# datalore.net
KiCad netlist of a schematic drawn in EAGLE
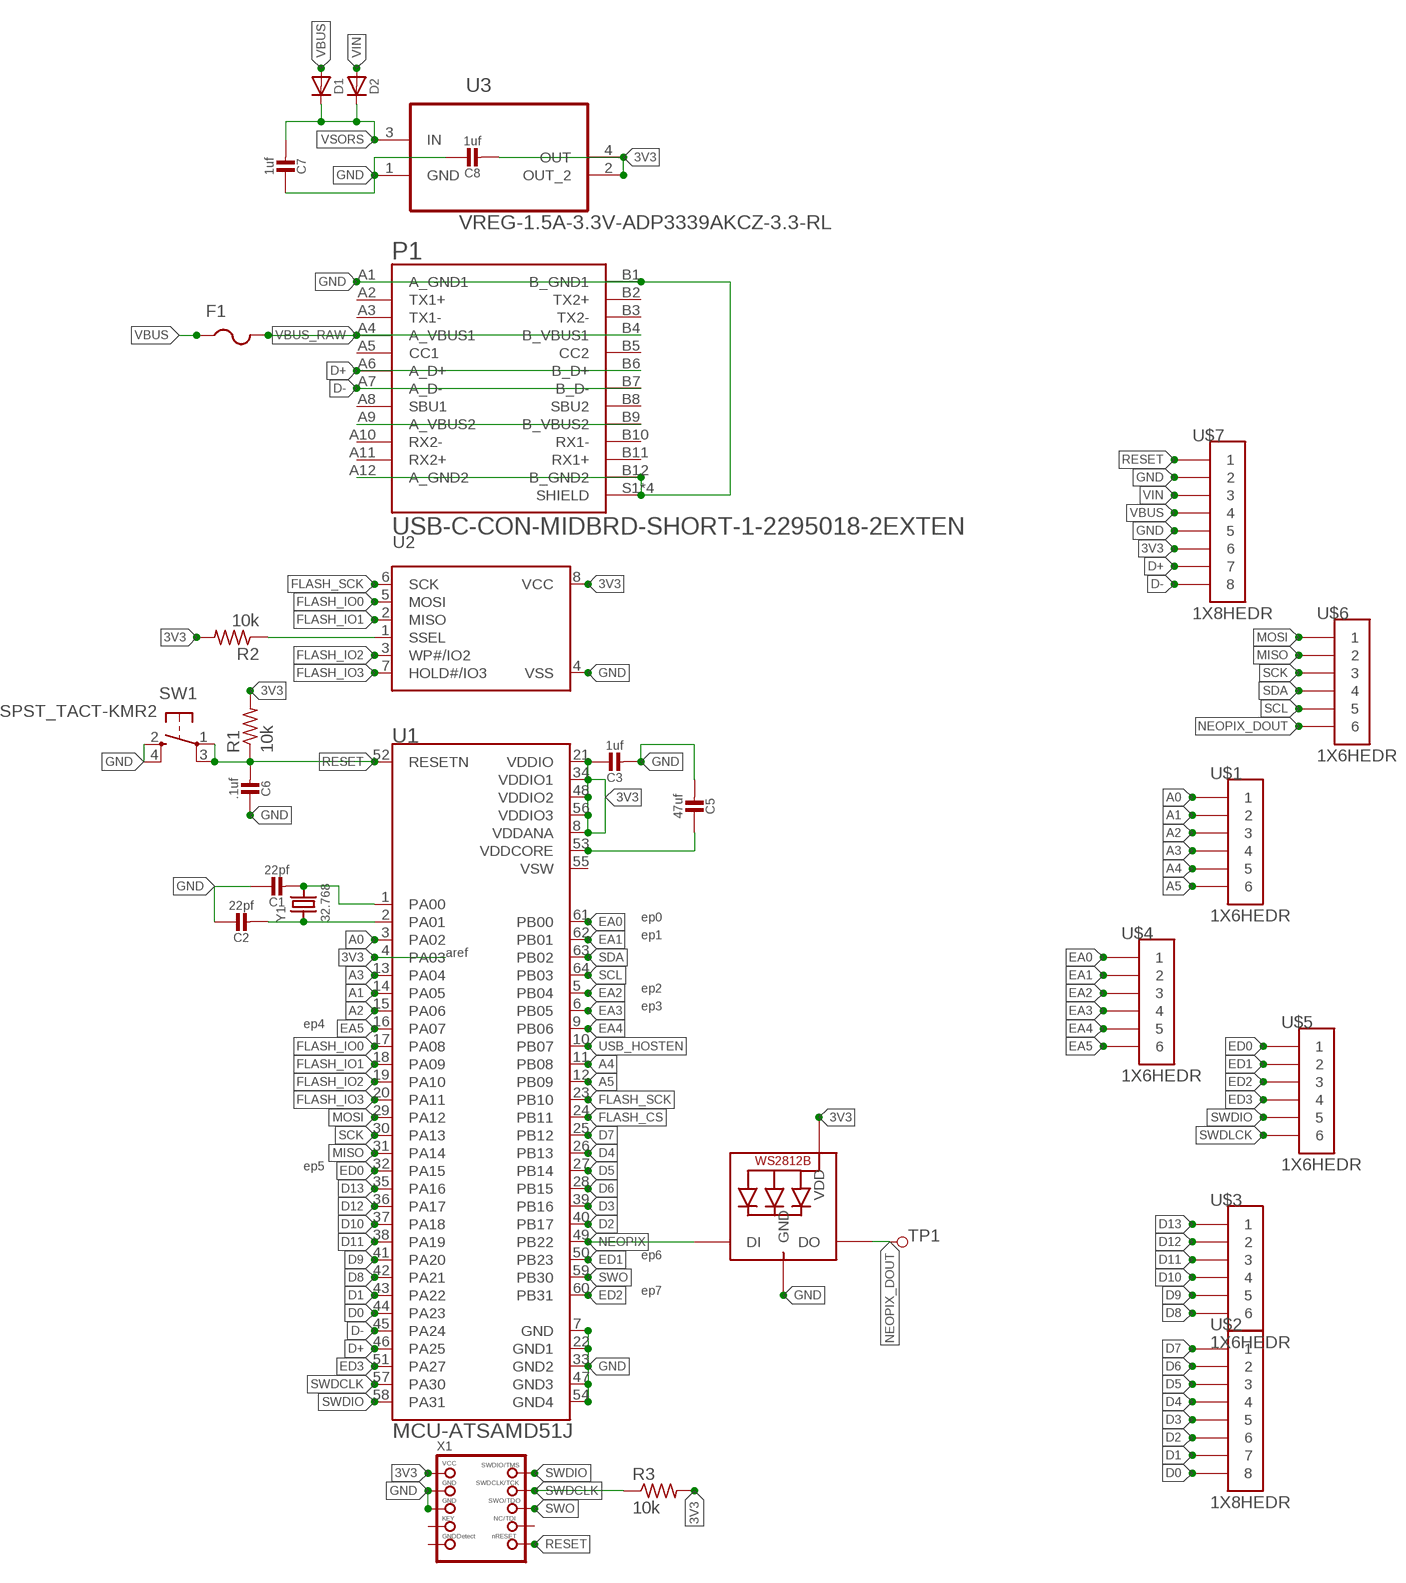
[diagram p0: schematic, sheet 1]

(export (version "E")
  (design (tool "Eeschema 10.0.6"))
  (components
    (comp (ref "C1")
      (value "22pf")
      (footprint "eagle-import:MICROBUILDER__0805")
      (libsource (lib "eagle-import") (part "C-US__0805"))
    )
    (comp (ref "C2")
      (value "22pf")
      (footprint "eagle-import:MICROBUILDER__0805")
      (libsource (lib "eagle-import") (part "C-US__0805"))
    )
    (comp (ref "C3")
      (value "1uf")
      (footprint "eagle-import:MICROBUILDER__0805")
      (libsource (lib "eagle-import") (part "C-US__0805"))
    )
    (comp (ref "C5")
      (value "47uf")
      (footprint "eagle-import:MICROBUILDER__0805")
      (libsource (lib "eagle-import") (part "C-US__0805"))
    )
    (comp (ref "C6")
      (value ".1uf")
      (footprint "eagle-import:MICROBUILDER__0805")
      (libsource (lib "eagle-import") (part "C-US__0805"))
    )
    (comp (ref "C7")
      (value "1uf")
      (footprint "eagle-import:MICROBUILDER__0805")
      (libsource (lib "eagle-import") (part "C-US__0805"))
    )
    (comp (ref "C8")
      (value "1uf")
      (footprint "eagle-import:MICROBUILDER__0805")
      (libsource (lib "eagle-import") (part "C-US__0805"))
    )
    (comp (ref "D1")
      (value "DIODESOD-123")
      (footprint "eagle-import:SOD-123")
      (libsource (lib "eagle-import") (part "DIODESOD-123"))
    )
    (comp (ref "D2")
      (value "DIODESOD-123")
      (footprint "eagle-import:SOD-123")
      (libsource (lib "eagle-import") (part "DIODESOD-123"))
    )
    (comp (ref "F1")
      (value "PTCFUSE-1206")
      (footprint "eagle-import:R1206")
      (libsource (lib "eagle-import") (part "PTCFUSE-1206"))
    )
    (comp (ref "LED1")
      (value "LED-NEO-WS2812B3535")
      (footprint "eagle-import:LED3535")
      (libsource (lib "eagle-import") (part "LED-NEO-WS2812B3535"))
    )
    (comp (ref "P1")
      (value "USB-C-CON-MIDBRD-SHORT-1-2295018-2EXTEN")
      (footprint "eagle-import:TE_1-2295018-2_EXTEN")
      (libsource (lib "eagle-import") (part "USB-C-CON-MIDBRD-SHORT-1-2295018-2EXTEN"))
    )
    (comp (ref "R1")
      (value "10k")
      (footprint "eagle-import:R0805")
      (libsource (lib "eagle-import") (part "R-US_R0805"))
    )
    (comp (ref "R2")
      (value "10k")
      (footprint "eagle-import:R0805")
      (libsource (lib "eagle-import") (part "R-US_R0805"))
    )
    (comp (ref "R3")
      (value "10k")
      (footprint "eagle-import:R0805")
      (libsource (lib "eagle-import") (part "R-US_R0805"))
    )
    (comp (ref "SW1")
      (value "SPST_TACT-KMR2")
      (footprint "eagle-import:KMR2")
      (libsource (lib "eagle-import") (part "SPST_TACT-KMR2"))
    )
    (comp (ref "TP1")
      (value "TESTPOINT_1X1")
      (footprint "eagle-import:1X1_POGO")
      (libsource (lib "eagle-import") (part "TESTPOINT_1X1"))
    )
    (comp (ref "U$1")
      (value "1X6HEDR")
      (footprint "eagle-import:1X6_HEDR")
      (libsource (lib "eagle-import") (part "1X6HEDR"))
    )
    (comp (ref "U$2")
      (value "1X8HEDR")
      (footprint "eagle-import:1X8_HEDR")
      (libsource (lib "eagle-import") (part "1X8HEDR"))
    )
    (comp (ref "U$3")
      (value "1X6HEDR")
      (footprint "eagle-import:1X6_HEDR")
      (libsource (lib "eagle-import") (part "1X6HEDR"))
    )
    (comp (ref "U$4")
      (value "1X6HEDR")
      (footprint "eagle-import:1X6_HEDR")
      (libsource (lib "eagle-import") (part "1X6HEDR"))
    )
    (comp (ref "U$5")
      (value "1X6HEDR")
      (footprint "eagle-import:1X6_HEDR")
      (libsource (lib "eagle-import") (part "1X6HEDR"))
    )
    (comp (ref "U$6")
      (value "1X6HEDR")
      (footprint "eagle-import:1X6_HEDR")
      (libsource (lib "eagle-import") (part "1X6HEDR"))
    )
    (comp (ref "U$7")
      (value "1X8HEDR")
      (footprint "eagle-import:1X8_HEDR")
      (libsource (lib "eagle-import") (part "1X8HEDR"))
    )
    (comp (ref "U1")
      (value "MCU-ATSAMD51J")
      (footprint "eagle-import:QFP50P1200X1200X120-64N")
      (fields (field (name "MF") "Microchip") (field (name "MP") "ATSAMD51J20A-AU"))
      (libsource (lib "eagle-import") (part "MCU-ATSAMD51J"))
    )
    (comp (ref "U2")
      (value "FLASH-SPI-SOIC8208MIL")
      (footprint "eagle-import:SOIC8_208MIL")
      (libsource (lib "eagle-import") (part "FLASH-SPI-SOIC8208MIL"))
    )
    (comp (ref "U3")
      (value "VREG-1.5A-3.3V-ADP3339AKCZ-3.3-RL")
      (footprint "eagle-import:SOT230P700X180-4N")
      (fields (field (name "MF") "Analog Devices") (field (name "MP") "ADP3339AKCZ-3.3-RL"))
      (libsource (lib "eagle-import") (part "VREG-1.5A-3.3V-ADP3339AKCZ-3.3-RL"))
    )
    (comp (ref "X1")
      (value "INTRFC-JTAG-CORTEXBOXPOSTS")
      (footprint "eagle-import:2X05_1.27MM_BOX_POSTS")
      (libsource (lib "eagle-import") (part "INTRFC-JTAG-CORTEXBOXPOSTS"))
    )
    (comp (ref "Y1")
      (value "32.768")
      (footprint "eagle-import:MICROBUILDER_CRYSTAL_4.9X1.8")
      (libsource (lib "eagle-import") (part "XTAL_ADA4.9X1.8"))
    )
  )
  (nets
    (net (code "1") (name "/VSW") (class "Default")
      (node (ref "U1") (pin "55") (pinfunction "VSW_55") (pintype "power_in"))
    )
    (net (code "2") (name "3V3") (class "Default")
      (node (ref "C3") (pin "1") (pinfunction "1_1") (pintype "passive"))
      (node (ref "C8") (pin "2") (pinfunction "2_2") (pintype "passive"))
      (node (ref "LED1") (pin "2") (pinfunction "VDD_2") (pintype "power_in"))
      (node (ref "R1") (pin "2") (pinfunction "2_2") (pintype "passive"))
      (node (ref "R2") (pin "2") (pinfunction "2_2") (pintype "passive"))
      (node (ref "R3") (pin "2") (pinfunction "2_2") (pintype "passive"))
      (node (ref "U$7") (pin "6") (pinfunction "6_6") (pintype "bidirectional"))
      (node (ref "U1") (pin "21") (pinfunction "VDDIO_21") (pintype "power_in"))
      (node (ref "U1") (pin "34") (pinfunction "VDDIO1_34") (pintype "power_in"))
      (node (ref "U1") (pin "4") (pinfunction "PA03_4") (pintype "bidirectional"))
      (node (ref "U1") (pin "48") (pinfunction "VDDIO2_48") (pintype "power_in"))
      (node (ref "U1") (pin "56") (pinfunction "VDDIO3_56") (pintype "power_in"))
      (node (ref "U1") (pin "8") (pinfunction "VDDANA_8") (pintype "power_in"))
      (node (ref "U2") (pin "8") (pinfunction "VCC_8") (pintype "bidirectional"))
      (node (ref "U3") (pin "2") (pinfunction "OUT_2_2") (pintype "output"))
      (node (ref "U3") (pin "4") (pinfunction "OUT_4") (pintype "output"))
      (node (ref "X1") (pin "1") (pinfunction "VCC_1") (pintype "power_in"))
    )
    (net (code "3") (name "A0") (class "Default")
      (node (ref "U$1") (pin "1") (pinfunction "1_1") (pintype "bidirectional"))
      (node (ref "U1") (pin "3") (pinfunction "PA02_3") (pintype "bidirectional"))
    )
    (net (code "4") (name "A1") (class "Default")
      (node (ref "U$1") (pin "2") (pinfunction "2_2") (pintype "bidirectional"))
      (node (ref "U1") (pin "14") (pinfunction "PA05_14") (pintype "bidirectional"))
    )
    (net (code "5") (name "A2") (class "Default")
      (node (ref "U$1") (pin "3") (pinfunction "3_3") (pintype "bidirectional"))
      (node (ref "U1") (pin "15") (pinfunction "PA06_15") (pintype "bidirectional"))
    )
    (net (code "6") (name "A3") (class "Default")
      (node (ref "U$1") (pin "4") (pinfunction "4_4") (pintype "bidirectional"))
      (node (ref "U1") (pin "13") (pinfunction "PA04_13") (pintype "bidirectional"))
    )
    (net (code "7") (name "A4") (class "Default")
      (node (ref "U$1") (pin "5") (pinfunction "5_5") (pintype "bidirectional"))
      (node (ref "U1") (pin "11") (pinfunction "PB08_11") (pintype "bidirectional"))
    )
    (net (code "8") (name "A5") (class "Default")
      (node (ref "U$1") (pin "6") (pinfunction "6_6") (pintype "bidirectional"))
      (node (ref "U1") (pin "12") (pinfunction "PB09_12") (pintype "bidirectional"))
    )
    (net (code "9") (name "D+") (class "Default")
      (node (ref "P1") (pin "A6") (pinfunction "A_D+_A6") (pintype "passive"))
      (node (ref "P1") (pin "B6") (pinfunction "B_D+_B6") (pintype "passive"))
      (node (ref "U$7") (pin "7") (pinfunction "7_7") (pintype "bidirectional"))
      (node (ref "U1") (pin "46") (pinfunction "PA25_46") (pintype "bidirectional"))
    )
    (net (code "10") (name "D-") (class "Default")
      (node (ref "P1") (pin "A7") (pinfunction "A_D-_A7") (pintype "passive"))
      (node (ref "P1") (pin "B7") (pinfunction "B_D-_B7") (pintype "passive"))
      (node (ref "U$7") (pin "8") (pinfunction "8_8") (pintype "bidirectional"))
      (node (ref "U1") (pin "45") (pinfunction "PA24_45") (pintype "bidirectional"))
    )
    (net (code "11") (name "D0") (class "Default")
      (node (ref "U$2") (pin "8") (pinfunction "8_8") (pintype "bidirectional"))
      (node (ref "U1") (pin "44") (pinfunction "PA23_44") (pintype "bidirectional"))
    )
    (net (code "12") (name "D1") (class "Default")
      (node (ref "U$2") (pin "7") (pinfunction "7_7") (pintype "bidirectional"))
      (node (ref "U1") (pin "43") (pinfunction "PA22_43") (pintype "bidirectional"))
    )
    (net (code "13") (name "D2") (class "Default")
      (node (ref "U$2") (pin "6") (pinfunction "6_6") (pintype "bidirectional"))
      (node (ref "U1") (pin "40") (pinfunction "PB17_40") (pintype "bidirectional"))
    )
    (net (code "14") (name "D3") (class "Default")
      (node (ref "U$2") (pin "5") (pinfunction "5_5") (pintype "bidirectional"))
      (node (ref "U1") (pin "39") (pinfunction "PB16_39") (pintype "bidirectional"))
    )
    (net (code "15") (name "D4") (class "Default")
      (node (ref "U$2") (pin "4") (pinfunction "4_4") (pintype "bidirectional"))
      (node (ref "U1") (pin "26") (pinfunction "PB13_26") (pintype "bidirectional"))
    )
    (net (code "16") (name "D5") (class "Default")
      (node (ref "U$2") (pin "3") (pinfunction "3_3") (pintype "bidirectional"))
      (node (ref "U1") (pin "27") (pinfunction "PB14_27") (pintype "bidirectional"))
    )
    (net (code "17") (name "D6") (class "Default")
      (node (ref "U$2") (pin "2") (pinfunction "2_2") (pintype "bidirectional"))
      (node (ref "U1") (pin "28") (pinfunction "PB15_28") (pintype "bidirectional"))
    )
    (net (code "18") (name "D7") (class "Default")
      (node (ref "U$2") (pin "1") (pinfunction "1_1") (pintype "bidirectional"))
      (node (ref "U1") (pin "25") (pinfunction "PB12_25") (pintype "bidirectional"))
    )
    (net (code "19") (name "D8") (class "Default")
      (node (ref "U$3") (pin "6") (pinfunction "6_6") (pintype "bidirectional"))
      (node (ref "U1") (pin "42") (pinfunction "PA21_42") (pintype "bidirectional"))
    )
    (net (code "20") (name "D9") (class "Default")
      (node (ref "U$3") (pin "5") (pinfunction "5_5") (pintype "bidirectional"))
      (node (ref "U1") (pin "41") (pinfunction "PA20_41") (pintype "bidirectional"))
    )
    (net (code "21") (name "D10") (class "Default")
      (node (ref "U$3") (pin "4") (pinfunction "4_4") (pintype "bidirectional"))
      (node (ref "U1") (pin "37") (pinfunction "PA18_37") (pintype "bidirectional"))
    )
    (net (code "22") (name "D11") (class "Default")
      (node (ref "U$3") (pin "3") (pinfunction "3_3") (pintype "bidirectional"))
      (node (ref "U1") (pin "38") (pinfunction "PA19_38") (pintype "bidirectional"))
    )
    (net (code "23") (name "D12") (class "Default")
      (node (ref "U$3") (pin "2") (pinfunction "2_2") (pintype "bidirectional"))
      (node (ref "U1") (pin "36") (pinfunction "PA17_36") (pintype "bidirectional"))
    )
    (net (code "24") (name "D13") (class "Default")
      (node (ref "U$3") (pin "1") (pinfunction "1_1") (pintype "bidirectional"))
      (node (ref "U1") (pin "35") (pinfunction "PA16_35") (pintype "bidirectional"))
    )
    (net (code "25") (name "EA0") (class "Default")
      (node (ref "U$4") (pin "1") (pinfunction "1_1") (pintype "bidirectional"))
      (node (ref "U1") (pin "61") (pinfunction "PB00_61") (pintype "bidirectional"))
    )
    (net (code "26") (name "EA1") (class "Default")
      (node (ref "U$4") (pin "2") (pinfunction "2_2") (pintype "bidirectional"))
      (node (ref "U1") (pin "62") (pinfunction "PB01_62") (pintype "bidirectional"))
    )
    (net (code "27") (name "EA2") (class "Default")
      (node (ref "U$4") (pin "3") (pinfunction "3_3") (pintype "bidirectional"))
      (node (ref "U1") (pin "5") (pinfunction "PB04_5") (pintype "bidirectional"))
    )
    (net (code "28") (name "EA3") (class "Default")
      (node (ref "U$4") (pin "4") (pinfunction "4_4") (pintype "bidirectional"))
      (node (ref "U1") (pin "6") (pinfunction "PB05_6") (pintype "bidirectional"))
    )
    (net (code "29") (name "EA4") (class "Default")
      (node (ref "U$4") (pin "5") (pinfunction "5_5") (pintype "bidirectional"))
      (node (ref "U1") (pin "9") (pinfunction "PB06_9") (pintype "bidirectional"))
    )
    (net (code "30") (name "EA5") (class "Default")
      (node (ref "U$4") (pin "6") (pinfunction "6_6") (pintype "bidirectional"))
      (node (ref "U1") (pin "16") (pinfunction "PA07_16") (pintype "bidirectional"))
    )
    (net (code "31") (name "ED0") (class "Default")
      (node (ref "U$5") (pin "1") (pinfunction "1_1") (pintype "bidirectional"))
      (node (ref "U1") (pin "32") (pinfunction "PA15_32") (pintype "bidirectional"))
    )
    (net (code "32") (name "ED1") (class "Default")
      (node (ref "U$5") (pin "2") (pinfunction "2_2") (pintype "bidirectional"))
      (node (ref "U1") (pin "50") (pinfunction "PB23_50") (pintype "bidirectional"))
    )
    (net (code "33") (name "ED2") (class "Default")
      (node (ref "U$5") (pin "3") (pinfunction "3_3") (pintype "bidirectional"))
      (node (ref "U1") (pin "60") (pinfunction "PB31_60") (pintype "bidirectional"))
    )
    (net (code "34") (name "ED3") (class "Default")
      (node (ref "U$5") (pin "4") (pinfunction "4_4") (pintype "bidirectional"))
      (node (ref "U1") (pin "51") (pinfunction "PA27_51") (pintype "bidirectional"))
    )
    (net (code "35") (name "FLASH_CS") (class "Default")
      (node (ref "U1") (pin "24") (pinfunction "PB11_24") (pintype "bidirectional"))
    )
    (net (code "36") (name "FLASH_IO0") (class "Default")
      (node (ref "U1") (pin "17") (pinfunction "PA08_17") (pintype "bidirectional"))
      (node (ref "U2") (pin "5") (pinfunction "MOSI_5") (pintype "bidirectional"))
    )
    (net (code "37") (name "FLASH_IO1") (class "Default")
      (node (ref "U1") (pin "18") (pinfunction "PA09_18") (pintype "bidirectional"))
      (node (ref "U2") (pin "2") (pinfunction "MISO_2") (pintype "bidirectional"))
    )
    (net (code "38") (name "FLASH_IO2") (class "Default")
      (node (ref "U1") (pin "19") (pinfunction "PA10_19") (pintype "bidirectional"))
      (node (ref "U2") (pin "3") (pinfunction "WP#/IO2_3") (pintype "bidirectional"))
    )
    (net (code "39") (name "FLASH_IO3") (class "Default")
      (node (ref "U1") (pin "20") (pinfunction "PA11_20") (pintype "bidirectional"))
      (node (ref "U2") (pin "7") (pinfunction "HOLD#/IO3_7") (pintype "bidirectional"))
    )
    (net (code "40") (name "FLASH_SCK") (class "Default")
      (node (ref "U1") (pin "23") (pinfunction "PB10_23") (pintype "bidirectional"))
      (node (ref "U2") (pin "6") (pinfunction "SCK_6") (pintype "bidirectional"))
    )
    (net (code "41") (name "GND") (class "Default")
      (node (ref "C1") (pin "1") (pinfunction "1_1") (pintype "passive"))
      (node (ref "C2") (pin "1") (pinfunction "1_1") (pintype "passive"))
      (node (ref "C3") (pin "2") (pinfunction "2_2") (pintype "passive"))
      (node (ref "C5") (pin "2") (pinfunction "2_2") (pintype "passive"))
      (node (ref "C6") (pin "1") (pinfunction "1_1") (pintype "passive"))
      (node (ref "C7") (pin "1") (pinfunction "1_1") (pintype "passive"))
      (node (ref "C8") (pin "1") (pinfunction "1_1") (pintype "passive"))
      (node (ref "LED1") (pin "4") (pinfunction "GND_4") (pintype "power_in"))
      (node (ref "P1") (pin "A1") (pinfunction "A_GND1_A1") (pintype "passive"))
      (node (ref "P1") (pin "A12") (pinfunction "A_GND2_A12") (pintype "passive"))
      (node (ref "P1") (pin "B1") (pinfunction "B_GND1_B1") (pintype "passive"))
      (node (ref "P1") (pin "B12") (pinfunction "B_GND2_B12") (pintype "passive"))
      (node (ref "P1") (pin "S1") (pinfunction "SHIELD_S1") (pintype "passive"))
      (node (ref "P1") (pin "S2") (pinfunction "SHIELD_S2") (pintype "passive"))
      (node (ref "P1") (pin "S3") (pinfunction "SHIELD_S3") (pintype "passive"))
      (node (ref "P1") (pin "S4") (pinfunction "SHIELD_S4") (pintype "passive"))
      (node (ref "SW1") (pin "2") (pinfunction "S_2") (pintype "passive"))
      (node (ref "SW1") (pin "4") (pinfunction "S1_4") (pintype "passive"))
      (node (ref "U$7") (pin "2") (pinfunction "2_2") (pintype "bidirectional"))
      (node (ref "U$7") (pin "5") (pinfunction "5_5") (pintype "bidirectional"))
      (node (ref "U1") (pin "22") (pinfunction "GND1_22") (pintype "power_in"))
      (node (ref "U1") (pin "33") (pinfunction "GND2_33") (pintype "power_in"))
      (node (ref "U1") (pin "47") (pinfunction "GND3_47") (pintype "power_in"))
      (node (ref "U1") (pin "54") (pinfunction "GND4_54") (pintype "power_in"))
      (node (ref "U1") (pin "7") (pinfunction "GND_7") (pintype "power_in"))
      (node (ref "U2") (pin "4") (pinfunction "VSS_4") (pintype "bidirectional"))
      (node (ref "U3") (pin "1") (pinfunction "GND_1") (pintype "passive"))
      (node (ref "X1") (pin "3") (pinfunction "GND_3") (pintype "power_in"))
      (node (ref "X1") (pin "5") (pinfunction "GND_5") (pintype "power_in"))
    )
    (net (code "42") (name "MISO") (class "Default")
      (node (ref "U$6") (pin "2") (pinfunction "2_2") (pintype "bidirectional"))
      (node (ref "U1") (pin "31") (pinfunction "PA14_31") (pintype "bidirectional"))
    )
    (net (code "43") (name "MOSI") (class "Default")
      (node (ref "U$6") (pin "1") (pinfunction "1_1") (pintype "bidirectional"))
      (node (ref "U1") (pin "29") (pinfunction "PA12_29") (pintype "bidirectional"))
    )
    (net (code "44") (name "NEOPIX") (class "Default")
      (node (ref "LED1") (pin "1") (pinfunction "DI_1") (pintype "input"))
      (node (ref "U1") (pin "49") (pinfunction "PB22_49") (pintype "bidirectional"))
    )
    (net (code "45") (name "NEOPIX_DOUT") (class "Default")
      (node (ref "LED1") (pin "3") (pinfunction "DO_3") (pintype "output"))
      (node (ref "TP1") (pin "1") (pinfunction "P1_1") (pintype "bidirectional"))
      (node (ref "U$6") (pin "6") (pinfunction "6_6") (pintype "bidirectional"))
    )
    (net (code "46") (name "Net-(P1-A_VBUS2)") (class "Default")
      (node (ref "P1") (pin "A9") (pinfunction "A_VBUS2_A9") (pintype "passive"))
      (node (ref "P1") (pin "B9") (pinfunction "B_VBUS2_B9") (pintype "passive"))
    )
    (net (code "47") (name "Net-(U1-PA00)") (class "Default")
      (node (ref "C1") (pin "2") (pinfunction "2_2") (pintype "passive"))
      (node (ref "U1") (pin "1") (pinfunction "PA00_1") (pintype "bidirectional"))
      (node (ref "Y1") (pin "2") (pinfunction "2_2") (pintype "passive"))
    )
    (net (code "48") (name "Net-(U1-PA01)") (class "Default")
      (node (ref "C2") (pin "2") (pinfunction "2_2") (pintype "passive"))
      (node (ref "U1") (pin "2") (pinfunction "PA01_2") (pintype "bidirectional"))
      (node (ref "Y1") (pin "1") (pinfunction "1_1") (pintype "passive"))
    )
    (net (code "49") (name "Net-(U1-VDDCORE)") (class "Default")
      (node (ref "C5") (pin "1") (pinfunction "1_1") (pintype "passive"))
      (node (ref "U1") (pin "53") (pinfunction "VDDCORE_53") (pintype "power_in"))
    )
    (net (code "50") (name "Net-(U2-SSEL)") (class "Default")
      (node (ref "R2") (pin "1") (pinfunction "1_1") (pintype "passive"))
      (node (ref "U2") (pin "1") (pinfunction "SSEL_1") (pintype "bidirectional"))
    )
    (net (code "51") (name "RESET") (class "Default")
      (node (ref "C6") (pin "2") (pinfunction "2_2") (pintype "passive"))
      (node (ref "R1") (pin "1") (pinfunction "1_1") (pintype "passive"))
      (node (ref "SW1") (pin "1") (pinfunction "P_1") (pintype "passive"))
      (node (ref "SW1") (pin "3") (pinfunction "P1_3") (pintype "passive"))
      (node (ref "U$7") (pin "1") (pinfunction "1_1") (pintype "bidirectional"))
      (node (ref "U1") (pin "52") (pinfunction "RESETN_52") (pintype "input"))
      (node (ref "X1") (pin "10") (pinfunction "NRESET_10") (pintype "bidirectional"))
    )
    (net (code "52") (name "SCK") (class "Default")
      (node (ref "U$6") (pin "3") (pinfunction "3_3") (pintype "bidirectional"))
      (node (ref "U1") (pin "30") (pinfunction "PA13_30") (pintype "bidirectional"))
    )
    (net (code "53") (name "SCL") (class "Default")
      (node (ref "U$6") (pin "5") (pinfunction "5_5") (pintype "bidirectional"))
      (node (ref "U1") (pin "64") (pinfunction "PB03_64") (pintype "bidirectional"))
    )
    (net (code "54") (name "SDA") (class "Default")
      (node (ref "U$6") (pin "4") (pinfunction "4_4") (pintype "bidirectional"))
      (node (ref "U1") (pin "63") (pinfunction "PB02_63") (pintype "bidirectional"))
    )
    (net (code "55") (name "SWDCLK") (class "Default")
      (node (ref "R3") (pin "1") (pinfunction "1_1") (pintype "passive"))
      (node (ref "U1") (pin "57") (pinfunction "PA30_57") (pintype "bidirectional"))
      (node (ref "X1") (pin "4") (pinfunction "SWDCLK_4") (pintype "bidirectional"))
    )
    (net (code "56") (name "SWDIO") (class "Default")
      (node (ref "U$5") (pin "5") (pinfunction "5_5") (pintype "bidirectional"))
      (node (ref "U1") (pin "58") (pinfunction "PA31_58") (pintype "bidirectional"))
      (node (ref "X1") (pin "2") (pinfunction "SWDIO_2") (pintype "bidirectional"))
    )
    (net (code "57") (name "SWDLCK") (class "Default")
      (node (ref "U$5") (pin "6") (pinfunction "6_6") (pintype "bidirectional"))
    )
    (net (code "58") (name "SWO") (class "Default")
      (node (ref "U1") (pin "59") (pinfunction "PB30_59") (pintype "bidirectional"))
      (node (ref "X1") (pin "6") (pinfunction "SWO_6") (pintype "bidirectional"))
    )
    (net (code "59") (name "USB_HOSTEN") (class "Default")
      (node (ref "U1") (pin "10") (pinfunction "PB07_10") (pintype "bidirectional"))
    )
    (net (code "60") (name "VBUS") (class "Default")
      (node (ref "D1") (pin "A") (pinfunction "A_A") (pintype "passive"))
      (node (ref "F1") (pin "1") (pinfunction "1_1") (pintype "passive"))
      (node (ref "U$7") (pin "4") (pinfunction "4_4") (pintype "bidirectional"))
    )
    (net (code "61") (name "VBUS_RAW") (class "Default")
      (node (ref "F1") (pin "2") (pinfunction "2_2") (pintype "passive"))
      (node (ref "P1") (pin "A4") (pinfunction "A_VBUS1_A4") (pintype "passive"))
      (node (ref "P1") (pin "B4") (pinfunction "B_VBUS1_B4") (pintype "passive"))
    )
    (net (code "62") (name "VIN") (class "Default")
      (node (ref "D2") (pin "A") (pinfunction "A_A") (pintype "passive"))
      (node (ref "U$7") (pin "3") (pinfunction "3_3") (pintype "bidirectional"))
    )
    (net (code "63") (name "VSORS") (class "Default")
      (node (ref "C7") (pin "2") (pinfunction "2_2") (pintype "passive"))
      (node (ref "D1") (pin "C") (pinfunction "C_C") (pintype "passive"))
      (node (ref "D2") (pin "C") (pinfunction "C_C") (pintype "passive"))
      (node (ref "U3") (pin "3") (pinfunction "IN_3") (pintype "input"))
    )
    (net (code "64") (name "unconnected-(P1-CC1-PadA5)") (class "Default")
      (node (ref "P1") (pin "A5") (pinfunction "CC1_A5") (pintype "passive"))
    )
    (net (code "65") (name "unconnected-(P1-CC2-PadB5)") (class "Default")
      (node (ref "P1") (pin "B5") (pinfunction "CC2_B5") (pintype "passive"))
    )
    (net (code "66") (name "unconnected-(P1-RX1+-PadB11)") (class "Default")
      (node (ref "P1") (pin "B11") (pinfunction "RX1+_B11") (pintype "passive"))
    )
    (net (code "67") (name "unconnected-(P1-RX1--PadB10)") (class "Default")
      (node (ref "P1") (pin "B10") (pinfunction "RX1-_B10") (pintype "passive"))
    )
    (net (code "68") (name "unconnected-(P1-RX2+-PadA11)") (class "Default")
      (node (ref "P1") (pin "A11") (pinfunction "RX2+_A11") (pintype "passive"))
    )
    (net (code "69") (name "unconnected-(P1-RX2--PadA10)") (class "Default")
      (node (ref "P1") (pin "A10") (pinfunction "RX2-_A10") (pintype "passive"))
    )
    (net (code "70") (name "unconnected-(P1-SBU1-PadA8)") (class "Default")
      (node (ref "P1") (pin "A8") (pinfunction "SBU1_A8") (pintype "passive"))
    )
    (net (code "71") (name "unconnected-(P1-SBU2-PadB8)") (class "Default")
      (node (ref "P1") (pin "B8") (pinfunction "SBU2_B8") (pintype "passive"))
    )
    (net (code "72") (name "unconnected-(P1-TX1+-PadA2)") (class "Default")
      (node (ref "P1") (pin "A2") (pinfunction "TX1+_A2") (pintype "passive"))
    )
    (net (code "73") (name "unconnected-(P1-TX1--PadA3)") (class "Default")
      (node (ref "P1") (pin "A3") (pinfunction "TX1-_A3") (pintype "passive"))
    )
    (net (code "74") (name "unconnected-(P1-TX2+-PadB2)") (class "Default")
      (node (ref "P1") (pin "B2") (pinfunction "TX2+_B2") (pintype "passive"))
    )
    (net (code "75") (name "unconnected-(P1-TX2--PadB3)") (class "Default")
      (node (ref "P1") (pin "B3") (pinfunction "TX2-_B3") (pintype "passive"))
    )
    (net (code "76") (name "unconnected-(X1-GNDDETECT-Pad9)") (class "Default")
      (node (ref "X1") (pin "9") (pinfunction "GNDDETECT_9") (pintype "bidirectional"))
    )
    (net (code "77") (name "unconnected-(X1-KEY-Pad7)") (class "Default")
      (node (ref "X1") (pin "7") (pinfunction "KEY_7") (pintype "bidirectional"))
    )
    (net (code "78") (name "unconnected-(X1-TDI-Pad8)") (class "Default")
      (node (ref "X1") (pin "8") (pinfunction "TDI_8") (pintype "bidirectional"))
    )
  )
)
